# akabeacon_square_da14580.net
KiCad netlist of a schematic drawn in EAGLE
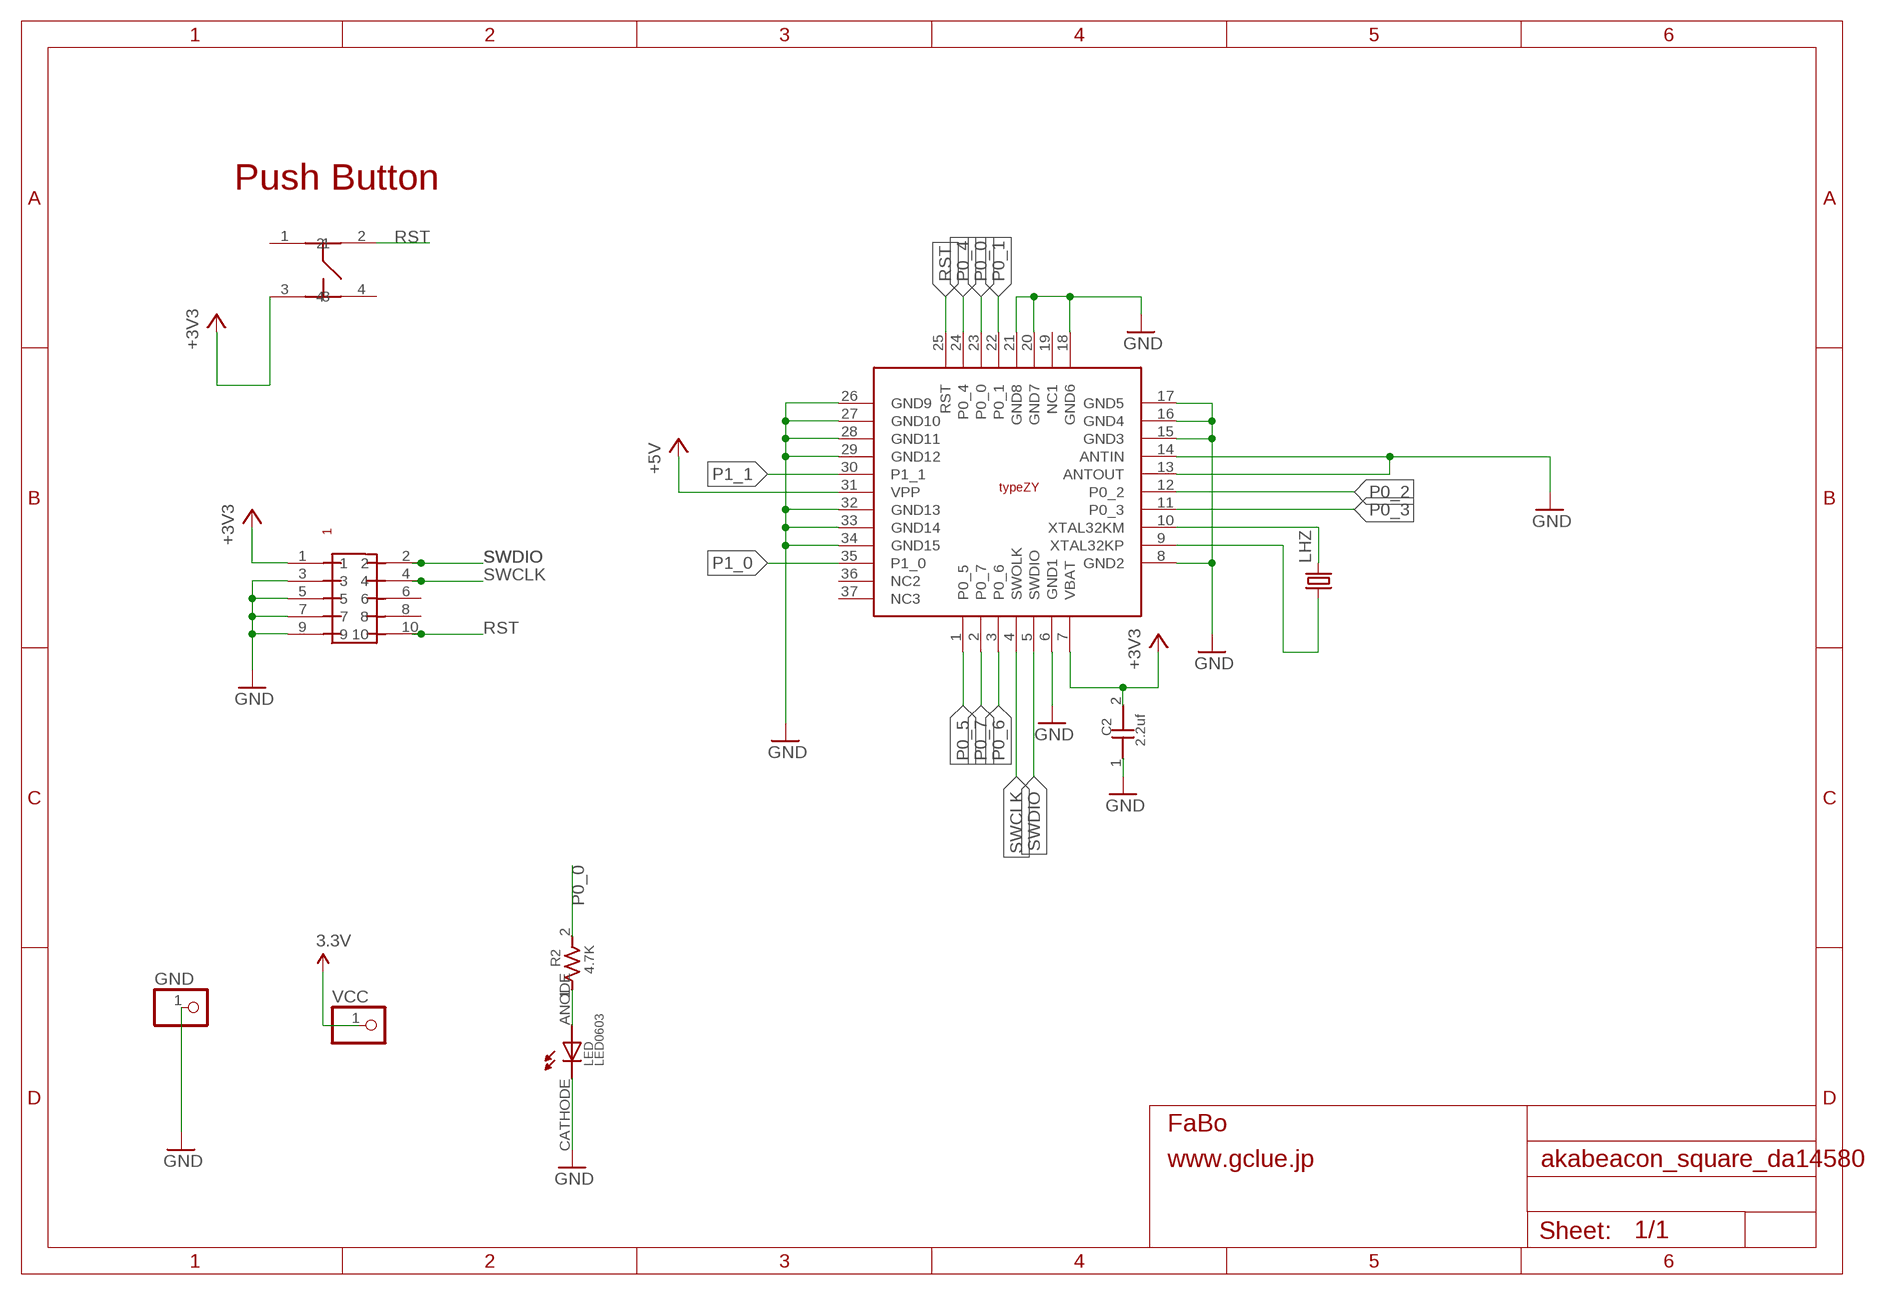
[diagram p0: schematic, sheet 1]

(export (version "E")
  (design (tool "Eeschema 10.0.6"))
  (components
    (comp (ref "C2")
      (value "2.2uf")
      (footprint "eagle-import:0603")
      (libsource (lib "eagle-import") (part "CAPACITOR0603"))
    )
    (comp (ref "GND")
      (value "PINHD-1X1CB")
      (footprint "eagle-import:1X01-CLEANBIG")
      (libsource (lib "eagle-import") (part "PINHD-1X1CB"))
    )
    (comp (ref "LED")
      (value "LED0603")
      (footprint "eagle-import:0603")
      (libsource (lib "eagle-import") (part "LED0603"))
    )
    (comp (ref "LHZ")
      (value "FC-12M")
      (footprint "eagle-import:FC-12M")
      (libsource (lib "eagle-import") (part "FC-12M"))
    )
    (comp (ref "R2")
      (value "4.7K")
      (footprint "eagle-import:0603")
      (libsource (lib "eagle-import") (part "RESISTOR0603"))
    )
    (comp (ref "U$6")
      (value "PIN-HEADER-SMT(1.27MM)2X5")
      (footprint "eagle-import:PIN-HEADER-SMT(1.27MM)2X5")
      (libsource (lib "eagle-import") (part "PIN-HEADER-SMT(1.27MM)2X5"))
    )
    (comp (ref "U$7")
      (value "SWICTH-4P(KMR2)")
      (footprint "eagle-import:SWITCH-4P(KMR2)")
      (libsource (lib "eagle-import") (part "SWICTH-4P(KMR2)"))
    )
    (comp (ref "U$9")
      (value "MURATA-TYPEZY")
      (footprint "eagle-import:MURATA_TYPEZY")
      (libsource (lib "eagle-import") (part "MURATA-TYPEZY"))
    )
    (comp (ref "VCC")
      (value "PINHD-1X1CB")
      (footprint "eagle-import:1X01-CLEANBIG")
      (libsource (lib "eagle-import") (part "PINHD-1X1CB"))
    )
  )
  (nets
    (net (code "1") (name "+3V3") (class "Default")
      (node (ref "C2") (pin "2") (pinfunction "2_2") (pintype "passive"))
      (node (ref "U$6") (pin "1") (pinfunction "1_1") (pintype "bidirectional"))
      (node (ref "U$7") (pin "3") (pinfunction "3_3") (pintype "bidirectional"))
      (node (ref "U$9") (pin "7") (pinfunction "VBAT_7") (pintype "bidirectional"))
    )
    (net (code "2") (name "+5V") (class "Default")
      (node (ref "U$9") (pin "31") (pinfunction "VPP_31") (pintype "bidirectional"))
    )
    (net (code "3") (name "3.3V") (class "Default")
      (node (ref "VCC") (pin "1") (pinfunction "1_1") (pintype "passive"))
    )
    (net (code "4") (name "GND") (class "Default")
      (node (ref "C2") (pin "1") (pinfunction "1_1") (pintype "passive"))
      (node (ref "GND") (pin "1") (pinfunction "1_1") (pintype "passive"))
      (node (ref "LED") (pin "CATHODE") (pinfunction "CATHODE_CATHODE") (pintype "passive"))
      (node (ref "U$6") (pin "3") (pinfunction "3_3") (pintype "bidirectional"))
      (node (ref "U$6") (pin "5") (pinfunction "5_5") (pintype "bidirectional"))
      (node (ref "U$6") (pin "7") (pinfunction "7_7") (pintype "bidirectional"))
      (node (ref "U$6") (pin "9") (pinfunction "9_9") (pintype "bidirectional"))
      (node (ref "U$9") (pin "13") (pinfunction "ANTOUT_13") (pintype "bidirectional"))
      (node (ref "U$9") (pin "14") (pinfunction "ANTIN_14") (pintype "bidirectional"))
      (node (ref "U$9") (pin "15") (pinfunction "GND3_15") (pintype "bidirectional"))
      (node (ref "U$9") (pin "16") (pinfunction "GND4_16") (pintype "bidirectional"))
      (node (ref "U$9") (pin "17") (pinfunction "GND5_17") (pintype "bidirectional"))
      (node (ref "U$9") (pin "18") (pinfunction "GND6_18") (pintype "bidirectional"))
      (node (ref "U$9") (pin "20") (pinfunction "GND7_20") (pintype "bidirectional"))
      (node (ref "U$9") (pin "21") (pinfunction "GND8_21") (pintype "bidirectional"))
      (node (ref "U$9") (pin "26") (pinfunction "GND9_26") (pintype "bidirectional"))
      (node (ref "U$9") (pin "27") (pinfunction "GND10_27") (pintype "bidirectional"))
      (node (ref "U$9") (pin "28") (pinfunction "GND11_28") (pintype "bidirectional"))
      (node (ref "U$9") (pin "29") (pinfunction "GND12_29") (pintype "bidirectional"))
      (node (ref "U$9") (pin "32") (pinfunction "GND13_32") (pintype "bidirectional"))
      (node (ref "U$9") (pin "33") (pinfunction "GND14_33") (pintype "bidirectional"))
      (node (ref "U$9") (pin "34") (pinfunction "GND15_34") (pintype "bidirectional"))
      (node (ref "U$9") (pin "6") (pinfunction "GND1_6") (pintype "bidirectional"))
      (node (ref "U$9") (pin "8") (pinfunction "GND2_8") (pintype "bidirectional"))
    )
    (net (code "5") (name "Net-(LED-PadANODE)") (class "Default")
      (node (ref "LED") (pin "ANODE") (pinfunction "ANODE_ANODE") (pintype "passive"))
      (node (ref "R2") (pin "1") (pinfunction "1_1") (pintype "passive"))
    )
    (net (code "6") (name "Net-(U$9-XTAL32KM)") (class "Default")
      (node (ref "LHZ") (pin "2") (pinfunction "2_2") (pintype "passive"))
      (node (ref "U$9") (pin "10") (pinfunction "XTAL32KM_10") (pintype "bidirectional"))
    )
    (net (code "7") (name "Net-(U$9-XTAL32KP)") (class "Default")
      (node (ref "LHZ") (pin "1") (pinfunction "1_1") (pintype "passive"))
      (node (ref "U$9") (pin "9") (pinfunction "XTAL32KP_9") (pintype "bidirectional"))
    )
    (net (code "8") (name "P0_0") (class "Default")
      (node (ref "R2") (pin "2") (pinfunction "2_2") (pintype "passive"))
      (node (ref "U$9") (pin "23") (pinfunction "P0_0_23") (pintype "bidirectional"))
    )
    (net (code "9") (name "P0_1") (class "Default")
      (node (ref "U$9") (pin "22") (pinfunction "P0_1_22") (pintype "bidirectional"))
    )
    (net (code "10") (name "P0_2") (class "Default")
      (node (ref "U$9") (pin "12") (pinfunction "P0_2_12") (pintype "bidirectional"))
    )
    (net (code "11") (name "P0_3") (class "Default")
      (node (ref "U$9") (pin "11") (pinfunction "P0_3_11") (pintype "bidirectional"))
    )
    (net (code "12") (name "P0_4") (class "Default")
      (node (ref "U$9") (pin "24") (pinfunction "P0_4_24") (pintype "bidirectional"))
    )
    (net (code "13") (name "P0_5") (class "Default")
      (node (ref "U$9") (pin "1") (pinfunction "P0_5_1") (pintype "bidirectional"))
    )
    (net (code "14") (name "P0_6") (class "Default")
      (node (ref "U$9") (pin "3") (pinfunction "P0_6_3") (pintype "bidirectional"))
    )
    (net (code "15") (name "P0_7") (class "Default")
      (node (ref "U$9") (pin "2") (pinfunction "P0_7_2") (pintype "bidirectional"))
    )
    (net (code "16") (name "P1_0") (class "Default")
      (node (ref "U$9") (pin "35") (pinfunction "P1_0_35") (pintype "bidirectional"))
    )
    (net (code "17") (name "P1_1") (class "Default")
      (node (ref "U$9") (pin "30") (pinfunction "P1_1_30") (pintype "bidirectional"))
    )
    (net (code "18") (name "RST") (class "Default")
      (node (ref "U$6") (pin "10") (pinfunction "10_10") (pintype "bidirectional"))
      (node (ref "U$7") (pin "2") (pinfunction "2_2") (pintype "bidirectional"))
      (node (ref "U$9") (pin "25") (pinfunction "RST_25") (pintype "bidirectional"))
    )
    (net (code "19") (name "SWCLK") (class "Default")
      (node (ref "U$6") (pin "4") (pinfunction "4_4") (pintype "bidirectional"))
      (node (ref "U$9") (pin "4") (pinfunction "SWOLK_4") (pintype "bidirectional"))
    )
    (net (code "20") (name "SWDIO") (class "Default")
      (node (ref "U$6") (pin "2") (pinfunction "2_2") (pintype "bidirectional"))
      (node (ref "U$9") (pin "5") (pinfunction "SWDIO_5") (pintype "bidirectional"))
    )
    (net (code "21") (name "unconnected-(U$6-Pad6)") (class "Default")
      (node (ref "U$6") (pin "6") (pinfunction "6_6") (pintype "bidirectional"))
    )
    (net (code "22") (name "unconnected-(U$6-Pad8)") (class "Default")
      (node (ref "U$6") (pin "8") (pinfunction "8_8") (pintype "bidirectional"))
    )
    (net (code "23") (name "unconnected-(U$7-Pad1)") (class "Default")
      (node (ref "U$7") (pin "1") (pinfunction "1_1") (pintype "bidirectional"))
    )
    (net (code "24") (name "unconnected-(U$7-Pad4)") (class "Default")
      (node (ref "U$7") (pin "4") (pinfunction "4_4") (pintype "bidirectional"))
    )
    (net (code "25") (name "unconnected-(U$9-NC1-Pad19)") (class "Default")
      (node (ref "U$9") (pin "19") (pinfunction "NC1_19") (pintype "bidirectional"))
    )
    (net (code "26") (name "unconnected-(U$9-NC2-Pad36)") (class "Default")
      (node (ref "U$9") (pin "36") (pinfunction "NC2_36") (pintype "bidirectional"))
    )
    (net (code "27") (name "unconnected-(U$9-NC3-Pad37)") (class "Default")
      (node (ref "U$9") (pin "37") (pinfunction "NC3_37") (pintype "bidirectional"))
    )
  )
)
